# V1_0.net
KiCad netlist of a schematic drawn in Altium Designer
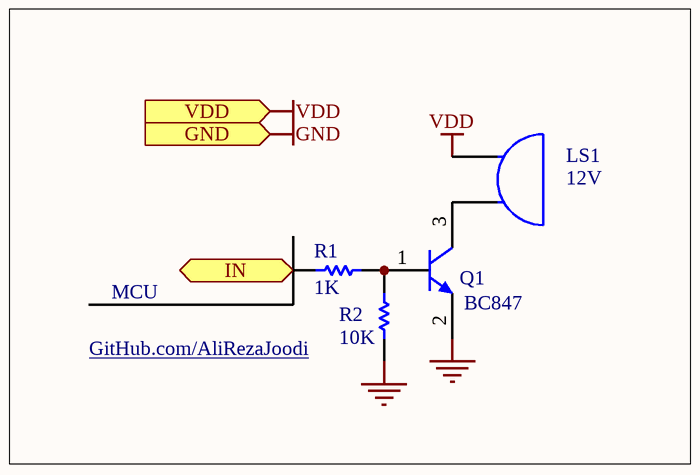
[diagram p0: V1.0.SchDoc]

(export (version "E")
  (design (tool "Eeschema 10.0.6"))
  (components
    (comp (ref "LS1")
      (value "12V")
      (footprint "RB_7.62mm")
      (description "Sounder")
      (fields
        (field (name "MANUFACTURER") "Generic Components")
        (field (name "Comment") "Buzzer")
        (field (name "PUBLISHER") "Altium Limited")
      )
      (libsource (lib "my Libraries") (part "Buzzer"))
    )
    (comp (ref "Q1")
      (value "BC847")
      (footprint "SOT23-3N")
      (description "Silicon Bipolar Transistor")
      (fields (field (name "Comment") "NPN"))
      (libsource (lib "my Libraries") (part "BC847"))
    )
    (comp (ref "R1")
      (value "1K")
      (footprint "0805")
      (description "Resistor")
      (fields (field (name "Comment") "Res1") (field (name "PUBLISHER") "Altium Limited"))
      (libsource (lib "Miscellaneous Devices") (part "Res1"))
    )
    (comp (ref "R2")
      (value "10K")
      (footprint "0805")
      (description "Resistor")
      (fields (field (name "Comment") "Res1") (field (name "PUBLISHER") "Altium Limited"))
      (libsource (lib "Miscellaneous Devices") (part "Res1"))
    )
  )
  (nets
    (net (code "1") (name "/IN") (class "Default")
      (node (ref "R1") (pin "2") (pinfunction "2_2") (pintype "passive"))
    )
    (net (code "2") (name "GND") (class "Default")
      (node (ref "Q1") (pin "2") (pinfunction "E_2") (pintype "passive"))
      (node (ref "R2") (pin "2") (pinfunction "2_2") (pintype "passive"))
    )
    (net (code "3") (name "Net-(LS1-B)") (class "Default")
      (node (ref "LS1") (pin "2") (pinfunction "B_2") (pintype "passive"))
      (node (ref "Q1") (pin "3") (pinfunction "C_3") (pintype "passive"))
    )
    (net (code "4") (name "Net-(Q1-B)") (class "Default")
      (node (ref "Q1") (pin "1") (pinfunction "B_1") (pintype "passive"))
      (node (ref "R1") (pin "1") (pinfunction "1_1") (pintype "passive"))
      (node (ref "R2") (pin "1") (pinfunction "1_1") (pintype "passive"))
    )
    (net (code "5") (name "VDD") (class "Default")
      (node (ref "LS1") (pin "1") (pinfunction "A_1") (pintype "passive"))
    )
  )
)
